# LCD_Screen.net
KiCad netlist of a schematic drawn in Altium Designer
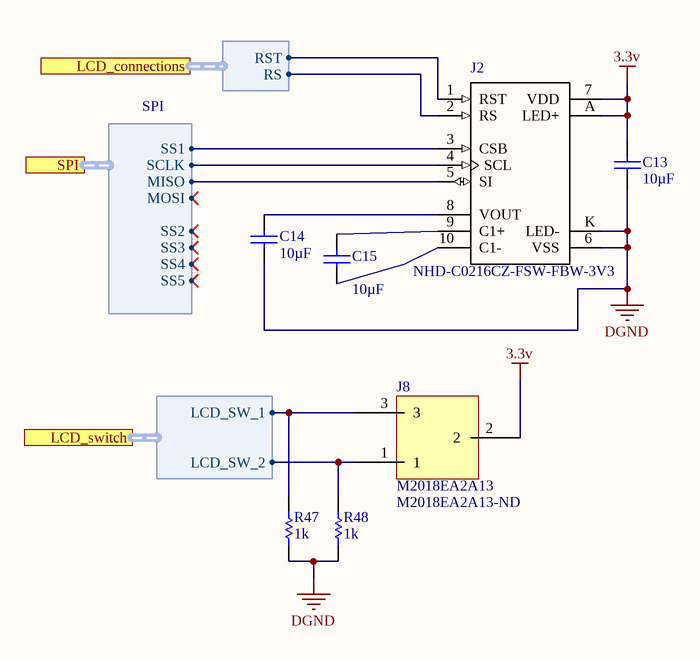
[diagram p0: LCD_Screen.SchDoc]

(export (version "E")
  (design (tool "Eeschema 10.0.6"))
  (components
    (comp (ref "C13")
      (value "C1608X5R1A106K080AC")
      (footprint "CAPC1608X90X20LL10")
      (description "Chip Capacitor, 10 uF, +/- 10%, 10 V, -55 to 85 degC, 0603 (1608 Metric), RoHS, Tape and Reel")
      (fields
        (field (name "PCN PART NUMBER") "MLCCPartNumberChange30/Nov/2012")
        (field (name "TOLERANCE") "±10%")
        (field (name "CAPACITANCE") "10µF")
      )
      (libsource (lib "Passives") (part "CMP-2000-04979-1"))
    )
    (comp (ref "C14")
      (value "C1608X5R1A106K080AC")
      (footprint "CAPC1608X90X20LL10")
      (description "Chip Capacitor, 10 uF, +/- 10%, 10 V, -55 to 85 degC, 0603 (1608 Metric), RoHS, Tape and Reel")
      (fields
        (field (name "PCN PART NUMBER") "MLCCPartNumberChange30/Nov/2012")
        (field (name "TOLERANCE") "±10%")
        (field (name "CAPACITANCE") "10µF")
      )
      (libsource (lib "Passives") (part "CMP-2000-04979-1"))
    )
    (comp (ref "C15")
      (value "C1608X5R1A106K080AC")
      (footprint "CAPC1608X90X20LL10")
      (description "Chip Capacitor, 10 uF, +/- 10%, 10 V, -55 to 85 degC, 0603 (1608 Metric), RoHS, Tape and Reel")
      (fields
        (field (name "PCN PART NUMBER") "MLCCPartNumberChange30/Nov/2012")
        (field (name "TOLERANCE") "±10%")
        (field (name "CAPACITANCE") "10µF")
      )
      (libsource (lib "Passives") (part "CMP-2000-04979-1"))
    )
    (comp (ref "J2")
      (value "NHD-C0216CZ-FSW-FBW-3V3")
      (footprint "*LCD_NHD-C0216CZ-FSW-FBW-3V3_NHD-C0216CZ-FSW-FBW-3V3(Primary)")
      (fields
        (field (name "MF") "Newhaven Display")
        (field (name "DIGI-KEY_PART_NUMBER") "NHD-C0216CZ-FSW-FBW-3V3-ND")
      )
      (libsource (lib "Components") (part "NHD-C0216CZ-FSW-FBW-3V3"))
    )
    (comp (ref "J8")
      (value "M2018EA2A13")
      (footprint "M2018EA2A13")
      (description "SWITCH TOGGLE SPDT 6A 125V")
      (fields
        (field (name "MANUFACTURER") "NKK Switches")
        (field (name "SUPPLIER PART NUMBER 1") "M2018EA2A13-ND")
      )
      (libsource (lib "Components") (part "M2018EA2A13"))
    )
    (comp (ref "R47")
      (value "1k")
      (footprint "RESC1608X55X30LL20T20")
      (fields (field (name "MANUFACTURER") "Panasonic") (field (name "PART NUMBER") "ERA3AEB102V"))
      (libsource (lib "Altium Content Vault") (part "RES"))
    )
    (comp (ref "R48")
      (value "1k")
      (footprint "RESC1608X55X30LL20T20")
      (fields (field (name "MANUFACTURER") "Panasonic") (field (name "PART NUMBER") "ERA3AEB102V"))
      (libsource (lib "Altium Content Vault") (part "RES"))
    )
  )
  (nets
    (net (code "4") (name "/LCD_SW_1") (class "Default")
      (node (ref "J8") (pin "3") (pinfunction "3_3") (pintype "passive"))
      (node (ref "R47") (pin "2") (pinfunction "2_2") (pintype "passive"))
    )
    (net (code "5") (name "/LCD_SW_2") (class "Default")
      (node (ref "J8") (pin "1") (pinfunction "1_1") (pintype "passive"))
      (node (ref "R48") (pin "2") (pinfunction "2_2") (pintype "passive"))
    )
    (net (code "6") (name "/MISO") (class "Default")
      (node (ref "J2") (pin "5") (pinfunction "SI_5") (pintype "bidirectional"))
    )
    (net (code "7") (name "/RS") (class "Default")
      (node (ref "J2") (pin "2") (pinfunction "RS_2") (pintype "input"))
    )
    (net (code "8") (name "/RST") (class "Default")
      (node (ref "J2") (pin "1") (pinfunction "RST_1") (pintype "input"))
    )
    (net (code "9") (name "/SCLK") (class "Default")
      (node (ref "J2") (pin "4") (pinfunction "SCL_4") (pintype "input"))
    )
    (net (code "10") (name "/SS1") (class "Default")
      (node (ref "J2") (pin "3") (pinfunction "CSB_3") (pintype "input"))
    )
    (net (code "14") (name "3.3v") (class "Default")
      (node (ref "C13") (pin "2") (pinfunction "2_2") (pintype "passive"))
      (node (ref "J2") (pin "7") (pinfunction "VDD_7") (pintype "power_in"))
      (node (ref "J2") (pin "A") (pinfunction "LED+_A") (pintype "power_in"))
      (node (ref "J8") (pin "2") (pinfunction "2_2") (pintype "passive"))
    )
    (net (code "15") (name "DGND") (class "Default")
      (node (ref "C13") (pin "1") (pinfunction "1_1") (pintype "passive"))
      (node (ref "C14") (pin "1") (pinfunction "1_1") (pintype "passive"))
      (node (ref "J2") (pin "6") (pinfunction "VSS_6") (pintype "power_in"))
      (node (ref "J2") (pin "K") (pinfunction "LED-_K") (pintype "power_in"))
      (node (ref "R47") (pin "1") (pinfunction "1_1") (pintype "passive"))
      (node (ref "R48") (pin "1") (pinfunction "1_1") (pintype "passive"))
    )
    (net (code "16") (name "Net-(J2-C1+)") (class "Default")
      (node (ref "C15") (pin "2") (pinfunction "2_2") (pintype "passive"))
      (node (ref "J2") (pin "9") (pinfunction "C1+_9") (pintype "passive"))
    )
    (net (code "17") (name "Net-(J2-C1-)") (class "Default")
      (node (ref "C15") (pin "1") (pinfunction "1_1") (pintype "passive"))
      (node (ref "J2") (pin "10") (pinfunction "C1-_10") (pintype "passive"))
    )
    (net (code "18") (name "Net-(J2-VOUT)") (class "Default")
      (node (ref "C14") (pin "2") (pinfunction "2_2") (pintype "passive"))
      (node (ref "J2") (pin "8") (pinfunction "VOUT_8") (pintype "passive"))
    )
  )
)
